# ZX_Distance_and_Gesture_Sensor.net
KiCad netlist of a schematic drawn in EAGLE
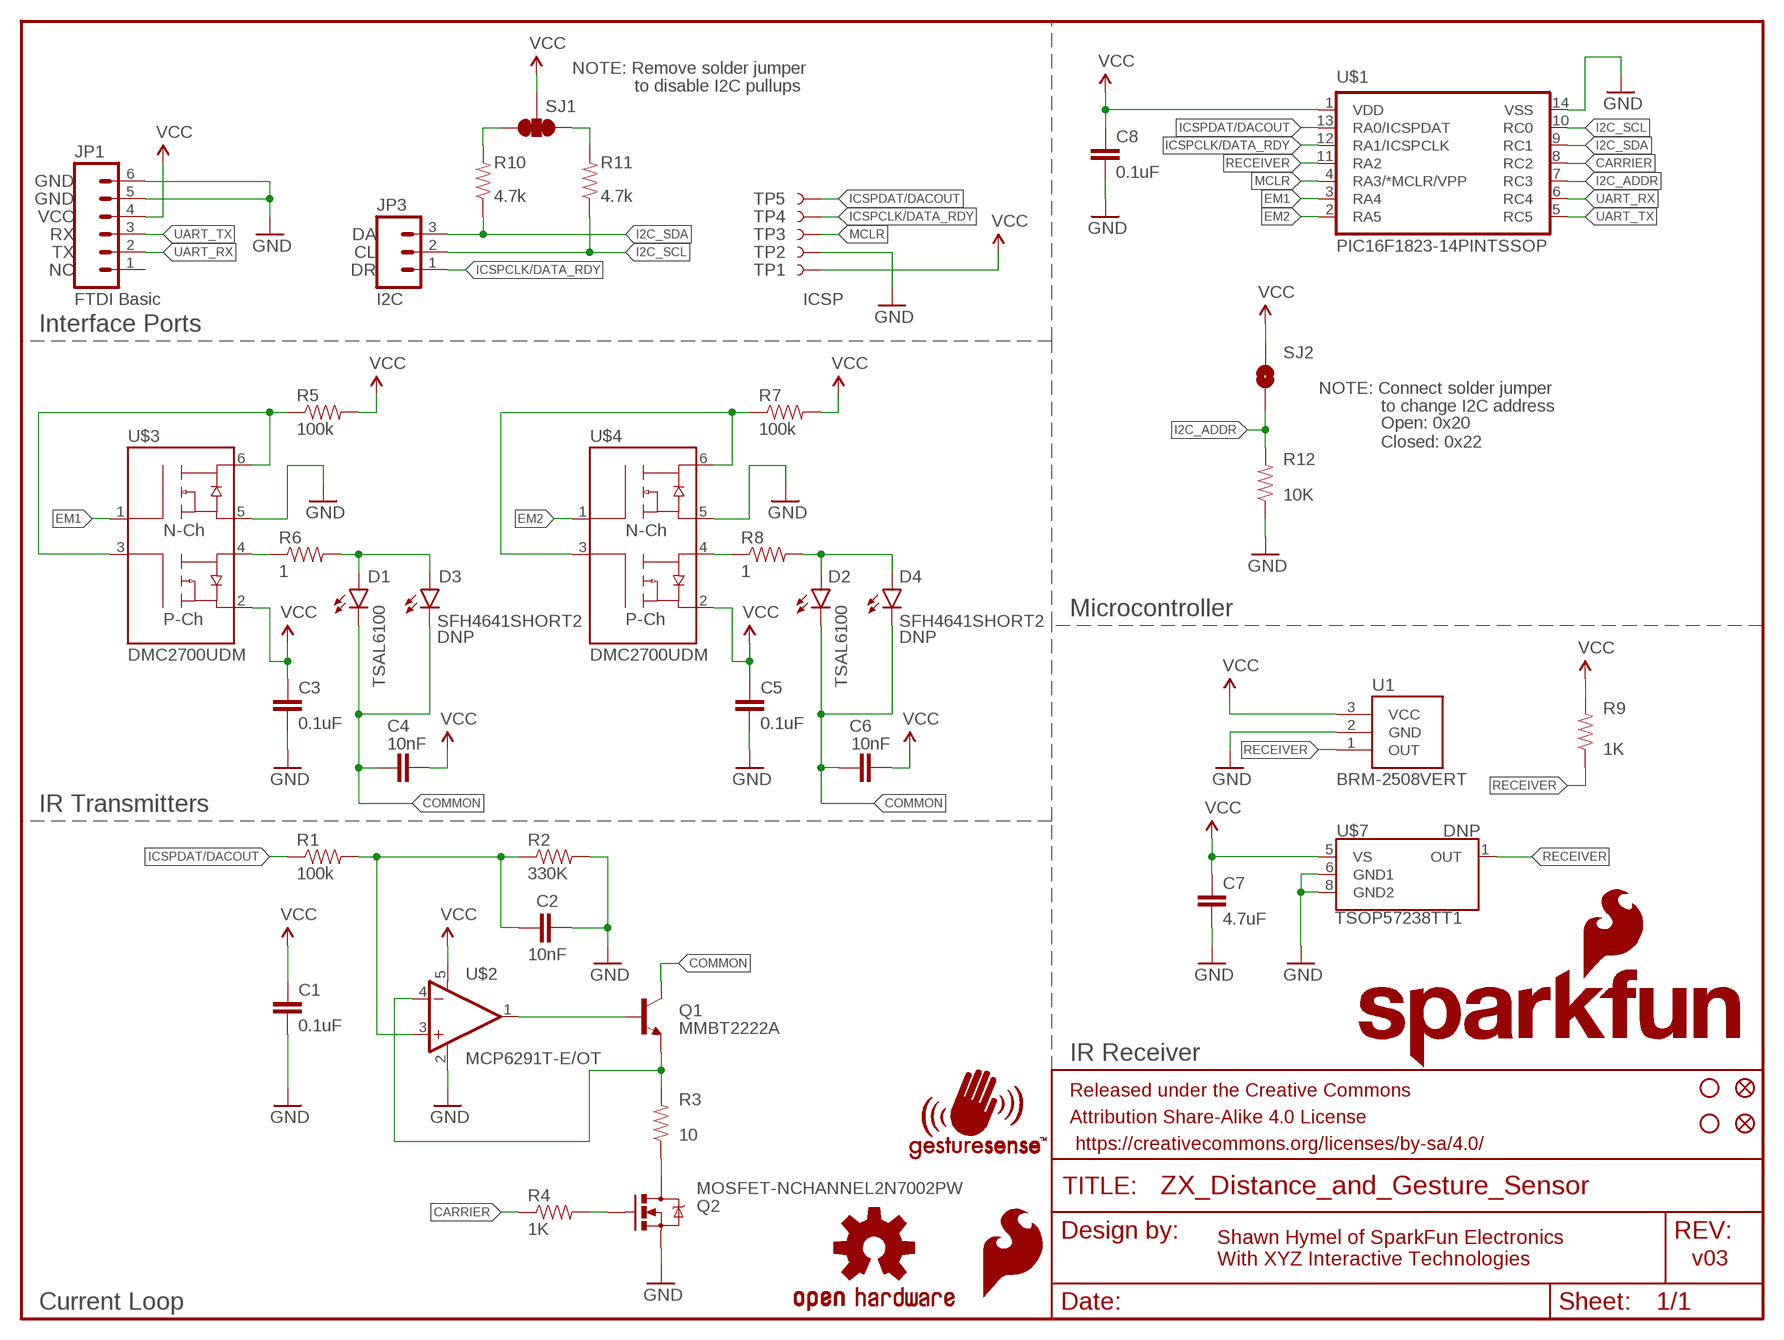
[diagram p0: schematic, sheet 1]

(export (version "E")
  (design (tool "Eeschema 10.0.6"))
  (components
    (comp (ref "C1")
      (value "0.1uF")
      (footprint "eagle-import:0603-CAP")
      (libsource (lib "eagle-import") (part "0.1UF-25V(+80/-20%)(0603)"))
    )
    (comp (ref "C2")
      (value "10nF")
      (footprint "eagle-import:0603-CAP")
      (libsource (lib "eagle-import") (part "10NF/10000PF-50V-10%(0603)"))
    )
    (comp (ref "C3")
      (value "0.1uF")
      (footprint "eagle-import:0603-CAP")
      (libsource (lib "eagle-import") (part "0.1UF-25V(+80/-20%)(0603)"))
    )
    (comp (ref "C4")
      (value "10nF")
      (footprint "eagle-import:0603-CAP")
      (libsource (lib "eagle-import") (part "10NF/10000PF-50V-10%(0603)"))
    )
    (comp (ref "C5")
      (value "0.1uF")
      (footprint "eagle-import:0603-CAP")
      (libsource (lib "eagle-import") (part "0.1UF-25V(+80/-20%)(0603)"))
    )
    (comp (ref "C6")
      (value "10nF")
      (footprint "eagle-import:0603-CAP")
      (libsource (lib "eagle-import") (part "10NF/10000PF-50V-10%(0603)"))
    )
    (comp (ref "C7")
      (value "4.7uF")
      (footprint "eagle-import:0603-CAP")
      (libsource (lib "eagle-import") (part "4.7UF-6.3V-10%(0603)0603"))
    )
    (comp (ref "C8")
      (value "0.1uF")
      (footprint "eagle-import:0603-CAP")
      (libsource (lib "eagle-import") (part "0.1UF-25V(+80/-20%)(0603)"))
    )
    (comp (ref "D1")
      (value "LED-IR-THRUTSAL6100")
      (footprint "eagle-import:LED5MM")
      (fields (field (name "VARIANT") "TSAL6100"))
      (libsource (lib "eagle-import") (part "LED-IR-THRUTSAL6100"))
    )
    (comp (ref "D2")
      (value "LED-IR-THRUTSAL6100")
      (footprint "eagle-import:LED5MM")
      (fields (field (name "VARIANT") "TSAL6100"))
      (libsource (lib "eagle-import") (part "LED-IR-THRUTSAL6100"))
    )
    (comp (ref "D3")
      (value "SFH4641SHORT2")
      (footprint "eagle-import:SFH4641-SHORT2")
      (libsource (lib "eagle-import") (part "SFH4641SHORT2"))
    )
    (comp (ref "D4")
      (value "SFH4641SHORT2")
      (footprint "eagle-import:SFH4641-SHORT2")
      (libsource (lib "eagle-import") (part "SFH4641SHORT2"))
    )
    (comp (ref "FID1")
      (value "FIDUCIAL1X2")
      (footprint "eagle-import:FIDUCIAL-1X2")
      (libsource (lib "eagle-import") (part "FIDUCIAL1X2"))
    )
    (comp (ref "FID2")
      (value "FIDUCIAL1X2")
      (footprint "eagle-import:FIDUCIAL-1X2")
      (libsource (lib "eagle-import") (part "FIDUCIAL1X2"))
    )
    (comp (ref "FRAME1")
      (value "FRAME-LETTER")
      (footprint "eagle-import:CREATIVE_COMMONS")
      (libsource (lib "eagle-import") (part "FRAME-LETTER"))
    )
    (comp (ref "JP1")
      (value "M06NO_SILK")
      (footprint "eagle-import:1X06_NO_SILK")
      (libsource (lib "eagle-import") (part "M06NO_SILK"))
    )
    (comp (ref "JP3")
      (value "M031X03_NO_SILK")
      (footprint "eagle-import:1X03_NO_SILK")
      (libsource (lib "eagle-import") (part "M031X03_NO_SILK"))
    )
    (comp (ref "LOGO1")
      (value "SFE_LOGO_FLAME.1_INCH")
      (footprint "eagle-import:SFE_LOGO_FLAME_.1")
      (libsource (lib "eagle-import") (part "SFE_LOGO_FLAME.1_INCH"))
    )
    (comp (ref "LOGO2")
      (value "OSHW-LOGOS")
      (footprint "eagle-import:OSHW-LOGO-S")
      (libsource (lib "eagle-import") (part "OSHW-LOGOS"))
    )
    (comp (ref "Q1")
      (value "MMBT2222A")
      (footprint "eagle-import:SOT23-3")
      (libsource (lib "eagle-import") (part "TRANSISTOR_NPNMMBT2222A"))
    )
    (comp (ref "Q2")
      (value "MOSFET-NCHANNEL2N7002PW")
      (footprint "eagle-import:SOT323")
      (libsource (lib "eagle-import") (part "MOSFET-NCHANNEL2N7002PW"))
    )
    (comp (ref "R1")
      (value "100k")
      (footprint "eagle-import:0603-RES")
      (libsource (lib "eagle-import") (part "100KOHM1/10W1%(0603)"))
    )
    (comp (ref "R2")
      (value "330K")
      (footprint "eagle-import:0603-RES")
      (libsource (lib "eagle-import") (part "330KOHM1/10W1%(0603)0603"))
    )
    (comp (ref "R3")
      (value "10")
      (footprint "eagle-import:0603-RES")
      (libsource (lib "eagle-import") (part "10OHM1/10W5%0603SMD"))
    )
    (comp (ref "R4")
      (value "1K")
      (footprint "eagle-import:0603-RES")
      (libsource (lib "eagle-import") (part "1KOHM1/10W1%(0603)"))
    )
    (comp (ref "R5")
      (value "100k")
      (footprint "eagle-import:0603-RES")
      (libsource (lib "eagle-import") (part "100KOHM1/10W1%(0603)"))
    )
    (comp (ref "R6")
      (value "1")
      (footprint "eagle-import:0603-RES")
      (libsource (lib "eagle-import") (part "1OHM1/10W1%(0603)"))
    )
    (comp (ref "R7")
      (value "100k")
      (footprint "eagle-import:0603-RES")
      (libsource (lib "eagle-import") (part "100KOHM1/10W1%(0603)"))
    )
    (comp (ref "R8")
      (value "1")
      (footprint "eagle-import:0603-RES")
      (libsource (lib "eagle-import") (part "1OHM1/10W1%(0603)"))
    )
    (comp (ref "R9")
      (value "1K")
      (footprint "eagle-import:0603-RES")
      (libsource (lib "eagle-import") (part "1KOHM1/10W1%(0603)"))
    )
    (comp (ref "R10")
      (value "4.7k")
      (footprint "eagle-import:0603")
      (libsource (lib "eagle-import") (part "4.7KOHM1/10W1%(0603)"))
    )
    (comp (ref "R11")
      (value "4.7k")
      (footprint "eagle-import:0603")
      (libsource (lib "eagle-import") (part "4.7KOHM1/10W1%(0603)"))
    )
    (comp (ref "R12")
      (value "10K")
      (footprint "eagle-import:0603-RES")
      (libsource (lib "eagle-import") (part "10KOHM1/10W1%(0603)0603"))
    )
    (comp (ref "SJ1")
      (value "SOLDERJUMPER_2WAYPASTE1&2&3")
      (footprint "eagle-import:SJ_3_PASTE1&2&3")
      (libsource (lib "eagle-import") (part "SOLDERJUMPER_2WAYPASTE1&2&3"))
    )
    (comp (ref "SJ2")
      (value "SOLDERJUMPERNO")
      (footprint "eagle-import:SJ_2S-NO")
      (libsource (lib "eagle-import") (part "SOLDERJUMPERNO"))
    )
    (comp (ref "STANDOFF1")
      (value "STAND-OFF")
      (footprint "eagle-import:STAND-OFF")
      (libsource (lib "eagle-import") (part "STAND-OFF"))
    )
    (comp (ref "STANDOFF2")
      (value "STAND-OFF")
      (footprint "eagle-import:STAND-OFF")
      (libsource (lib "eagle-import") (part "STAND-OFF"))
    )
    (comp (ref "TP1")
      (value "TEST-POINT3X4")
      (footprint "eagle-import:PAD.03X.04")
      (libsource (lib "eagle-import") (part "TEST-POINT3X4"))
    )
    (comp (ref "TP2")
      (value "TEST-POINT3X4")
      (footprint "eagle-import:PAD.03X.04")
      (libsource (lib "eagle-import") (part "TEST-POINT3X4"))
    )
    (comp (ref "TP3")
      (value "TEST-POINT3X4")
      (footprint "eagle-import:PAD.03X.04")
      (libsource (lib "eagle-import") (part "TEST-POINT3X4"))
    )
    (comp (ref "TP4")
      (value "TEST-POINT3X4")
      (footprint "eagle-import:PAD.03X.04")
      (libsource (lib "eagle-import") (part "TEST-POINT3X4"))
    )
    (comp (ref "TP5")
      (value "TEST-POINT3X4")
      (footprint "eagle-import:PAD.03X.04")
      (libsource (lib "eagle-import") (part "TEST-POINT3X4"))
    )
    (comp (ref "U$1")
      (value "PIC16F1823-14PINTSSOP")
      (footprint "eagle-import:TSSOP14")
      (libsource (lib "eagle-import") (part "PIC16F1823-14PINTSSOP"))
    )
    (comp (ref "U$2")
      (value "MCP6291T-E/OT")
      (footprint "eagle-import:SOT23-5")
      (libsource (lib "eagle-import") (part "MCP6291T-E/OT"))
    )
    (comp (ref "U$3")
      (value "DMC2700UDM")
      (footprint "eagle-import:SOT26")
      (libsource (lib "eagle-import") (part "DMC2700UDM"))
    )
    (comp (ref "U$4")
      (value "DMC2700UDM")
      (footprint "eagle-import:SOT26")
      (libsource (lib "eagle-import") (part "DMC2700UDM"))
    )
    (comp (ref "U$5")
      (value "SFE_LOGO_NAME_FLAME.1_INCH")
      (footprint "eagle-import:SFE_LOGO_NAME_FLAME_.1")
      (libsource (lib "eagle-import") (part "SFE_LOGO_NAME_FLAME.1_INCH"))
    )
    (comp (ref "U$6")
      (value "GESTURESENSE_LOGOSTEXT")
      (footprint "eagle-import:GESTURESENSE_TEXT")
      (libsource (lib "eagle-import") (part "GESTURESENSE_LOGOSTEXT"))
    )
    (comp (ref "U$7")
      (value "TSOP57238TT1")
      (footprint "eagle-import:TSOP572")
      (fields (field (name "PLACE") "DNP"))
      (libsource (lib "eagle-import") (part "TSOP57238TT1"))
    )
    (comp (ref "U1")
      (value "BRM-2508VERT")
      (footprint "eagle-import:BRM-2508_VERT")
      (libsource (lib "eagle-import") (part "BRM-2508VERT"))
    )
  )
  (nets
    (net (code "1") (name "CARRIER") (class "Default")
      (node (ref "R4") (pin "1") (pinfunction "1_1") (pintype "passive"))
      (node (ref "U$1") (pin "8") (pinfunction "RC2_8") (pintype "bidirectional"))
    )
    (net (code "2") (name "COMMON") (class "Default")
      (node (ref "C4") (pin "1") (pinfunction "1_1") (pintype "passive"))
      (node (ref "C6") (pin "1") (pinfunction "1_1") (pintype "passive"))
      (node (ref "D1") (pin "K") (pinfunction "C_K") (pintype "passive"))
      (node (ref "D2") (pin "K") (pinfunction "C_K") (pintype "passive"))
      (node (ref "D3") (pin "C") (pinfunction "C_C") (pintype "passive"))
      (node (ref "D4") (pin "C") (pinfunction "C_C") (pintype "passive"))
      (node (ref "Q1") (pin "3") (pinfunction "C_3") (pintype "passive"))
    )
    (net (code "3") (name "EM1") (class "Default")
      (node (ref "U$1") (pin "3") (pinfunction "RA4_3") (pintype "bidirectional"))
      (node (ref "U$3") (pin "1") (pinfunction "G1_1") (pintype "bidirectional"))
    )
    (net (code "4") (name "EM2") (class "Default")
      (node (ref "U$1") (pin "2") (pinfunction "RA5_2") (pintype "bidirectional"))
      (node (ref "U$4") (pin "1") (pinfunction "G1_1") (pintype "bidirectional"))
    )
    (net (code "5") (name "GND") (class "Default")
      (node (ref "C1") (pin "2") (pinfunction "2_2") (pintype "passive"))
      (node (ref "C2") (pin "2") (pinfunction "2_2") (pintype "passive"))
      (node (ref "C3") (pin "2") (pinfunction "2_2") (pintype "passive"))
      (node (ref "C5") (pin "2") (pinfunction "2_2") (pintype "passive"))
      (node (ref "C7") (pin "2") (pinfunction "2_2") (pintype "passive"))
      (node (ref "C8") (pin "2") (pinfunction "2_2") (pintype "passive"))
      (node (ref "JP1") (pin "5") (pinfunction "5_5") (pintype "passive"))
      (node (ref "JP1") (pin "6") (pinfunction "6_6") (pintype "passive"))
      (node (ref "Q2") (pin "2") (pinfunction "S_2") (pintype "passive"))
      (node (ref "R12") (pin "1") (pinfunction "1_1") (pintype "passive"))
      (node (ref "R2") (pin "2") (pinfunction "2_2") (pintype "passive"))
      (node (ref "TP2") (pin "P$1") (pinfunction "1_P$1") (pintype "bidirectional"))
      (node (ref "U$1") (pin "14") (pinfunction "VSS_14") (pintype "power_in"))
      (node (ref "U$2") (pin "2") (pinfunction "V-_2") (pintype "power_in"))
      (node (ref "U$3") (pin "5") (pinfunction "S1_5") (pintype "bidirectional"))
      (node (ref "U$4") (pin "5") (pinfunction "S1_5") (pintype "bidirectional"))
      (node (ref "U$7") (pin "6") (pinfunction "GND1_6") (pintype "bidirectional"))
      (node (ref "U$7") (pin "8") (pinfunction "GND2_8") (pintype "bidirectional"))
      (node (ref "U1") (pin "2") (pinfunction "GND_2") (pintype "bidirectional"))
    )
    (net (code "6") (name "I2C_ADDR") (class "Default")
      (node (ref "R12") (pin "2") (pinfunction "2_2") (pintype "passive"))
      (node (ref "SJ2") (pin "1") (pinfunction "1_1") (pintype "passive"))
      (node (ref "U$1") (pin "7") (pinfunction "RC3_7") (pintype "bidirectional"))
    )
    (net (code "7") (name "I2C_SCL") (class "Default")
      (node (ref "JP3") (pin "2") (pinfunction "2_2") (pintype "passive"))
      (node (ref "R11") (pin "1") (pinfunction "1_1") (pintype "passive"))
      (node (ref "U$1") (pin "10") (pinfunction "RC0_10") (pintype "bidirectional"))
    )
    (net (code "8") (name "I2C_SDA") (class "Default")
      (node (ref "JP3") (pin "3") (pinfunction "3_3") (pintype "passive"))
      (node (ref "R10") (pin "1") (pinfunction "1_1") (pintype "passive"))
      (node (ref "U$1") (pin "9") (pinfunction "RC1_9") (pintype "bidirectional"))
    )
    (net (code "9") (name "ICSPCLK{slash}DATA_RDY") (class "Default")
      (node (ref "JP3") (pin "1") (pinfunction "1_1") (pintype "passive"))
      (node (ref "TP4") (pin "P$1") (pinfunction "1_P$1") (pintype "bidirectional"))
      (node (ref "U$1") (pin "12") (pinfunction "RA1/ICSPCLK_12") (pintype "bidirectional"))
    )
    (net (code "10") (name "ICSPDAT{slash}DACOUT") (class "Default")
      (node (ref "R1") (pin "1") (pinfunction "1_1") (pintype "passive"))
      (node (ref "TP5") (pin "P$1") (pinfunction "1_P$1") (pintype "bidirectional"))
      (node (ref "U$1") (pin "13") (pinfunction "RA0/ICSPDAT_13") (pintype "bidirectional"))
    )
    (net (code "11") (name "MCLR") (class "Default")
      (node (ref "TP3") (pin "P$1") (pinfunction "1_P$1") (pintype "bidirectional"))
      (node (ref "U$1") (pin "4") (pinfunction "RA3/*MCLR/VPP_4") (pintype "input"))
    )
    (net (code "12") (name "Net-(D1-PadA)") (class "Default")
      (node (ref "D1") (pin "A") (pinfunction "A_A") (pintype "passive"))
      (node (ref "D3") (pin "A") (pinfunction "A_A") (pintype "passive"))
      (node (ref "R6") (pin "2") (pinfunction "2_2") (pintype "passive"))
    )
    (net (code "13") (name "Net-(D2-PadA)") (class "Default")
      (node (ref "D2") (pin "A") (pinfunction "A_A") (pintype "passive"))
      (node (ref "D4") (pin "A") (pinfunction "A_A") (pintype "passive"))
      (node (ref "R8") (pin "2") (pinfunction "2_2") (pintype "passive"))
    )
    (net (code "14") (name "Net-(Q1-B)") (class "Default")
      (node (ref "Q1") (pin "1") (pinfunction "B_1") (pintype "passive"))
      (node (ref "U$2") (pin "1") (pinfunction "OUT_1") (pintype "output"))
    )
    (net (code "15") (name "Net-(Q1-E)") (class "Default")
      (node (ref "Q1") (pin "2") (pinfunction "E_2") (pintype "passive"))
      (node (ref "R3") (pin "2") (pinfunction "2_2") (pintype "passive"))
      (node (ref "U$2") (pin "4") (pinfunction "-IN_4") (pintype "input"))
    )
    (net (code "16") (name "Net-(Q2-D)") (class "Default")
      (node (ref "Q2") (pin "3") (pinfunction "D_3") (pintype "passive"))
      (node (ref "R3") (pin "1") (pinfunction "1_1") (pintype "passive"))
    )
    (net (code "17") (name "Net-(Q2-G)") (class "Default")
      (node (ref "Q2") (pin "1") (pinfunction "G_1") (pintype "passive"))
      (node (ref "R4") (pin "2") (pinfunction "2_2") (pintype "passive"))
    )
    (net (code "18") (name "Net-(R10-Pad2)") (class "Default")
      (node (ref "R10") (pin "2") (pinfunction "2_2") (pintype "passive"))
      (node (ref "SJ1") (pin "3") (pinfunction "3_3") (pintype "passive"))
    )
    (net (code "19") (name "Net-(R11-Pad2)") (class "Default")
      (node (ref "R11") (pin "2") (pinfunction "2_2") (pintype "passive"))
      (node (ref "SJ1") (pin "1") (pinfunction "1_1") (pintype "passive"))
    )
    (net (code "20") (name "Net-(U$2-+IN)") (class "Default")
      (node (ref "C2") (pin "1") (pinfunction "1_1") (pintype "passive"))
      (node (ref "R1") (pin "2") (pinfunction "2_2") (pintype "passive"))
      (node (ref "R2") (pin "1") (pinfunction "1_1") (pintype "passive"))
      (node (ref "U$2") (pin "3") (pinfunction "+IN_3") (pintype "input"))
    )
    (net (code "21") (name "Net-(U$3-D1)") (class "Default")
      (node (ref "R5") (pin "1") (pinfunction "1_1") (pintype "passive"))
      (node (ref "U$3") (pin "3") (pinfunction "G2_3") (pintype "bidirectional"))
      (node (ref "U$3") (pin "6") (pinfunction "D1_6") (pintype "bidirectional"))
    )
    (net (code "22") (name "Net-(U$3-D2)") (class "Default")
      (node (ref "R6") (pin "1") (pinfunction "1_1") (pintype "passive"))
      (node (ref "U$3") (pin "4") (pinfunction "D2_4") (pintype "bidirectional"))
    )
    (net (code "23") (name "Net-(U$4-D1)") (class "Default")
      (node (ref "R7") (pin "1") (pinfunction "1_1") (pintype "passive"))
      (node (ref "U$4") (pin "3") (pinfunction "G2_3") (pintype "bidirectional"))
      (node (ref "U$4") (pin "6") (pinfunction "D1_6") (pintype "bidirectional"))
    )
    (net (code "24") (name "Net-(U$4-D2)") (class "Default")
      (node (ref "R8") (pin "1") (pinfunction "1_1") (pintype "passive"))
      (node (ref "U$4") (pin "4") (pinfunction "D2_4") (pintype "bidirectional"))
    )
    (net (code "25") (name "RECEIVER") (class "Default")
      (node (ref "R9") (pin "1") (pinfunction "1_1") (pintype "passive"))
      (node (ref "U$1") (pin "11") (pinfunction "RA2_11") (pintype "bidirectional"))
      (node (ref "U$7") (pin "1") (pinfunction "OUT_1") (pintype "bidirectional"))
      (node (ref "U1") (pin "1") (pinfunction "OUT_1") (pintype "bidirectional"))
    )
    (net (code "26") (name "UART_RX") (class "Default")
      (node (ref "JP1") (pin "2") (pinfunction "2_2") (pintype "passive"))
      (node (ref "U$1") (pin "6") (pinfunction "RC4_6") (pintype "bidirectional"))
    )
    (net (code "27") (name "UART_TX") (class "Default")
      (node (ref "JP1") (pin "3") (pinfunction "3_3") (pintype "passive"))
      (node (ref "U$1") (pin "5") (pinfunction "RC5_5") (pintype "bidirectional"))
    )
    (net (code "28") (name "VCC") (class "Default")
      (node (ref "C1") (pin "1") (pinfunction "1_1") (pintype "passive"))
      (node (ref "C3") (pin "1") (pinfunction "1_1") (pintype "passive"))
      (node (ref "C4") (pin "2") (pinfunction "2_2") (pintype "passive"))
      (node (ref "C5") (pin "1") (pinfunction "1_1") (pintype "passive"))
      (node (ref "C6") (pin "2") (pinfunction "2_2") (pintype "passive"))
      (node (ref "C7") (pin "1") (pinfunction "1_1") (pintype "passive"))
      (node (ref "C8") (pin "1") (pinfunction "1_1") (pintype "passive"))
      (node (ref "JP1") (pin "4") (pinfunction "4_4") (pintype "passive"))
      (node (ref "R5") (pin "2") (pinfunction "2_2") (pintype "passive"))
      (node (ref "R7") (pin "2") (pinfunction "2_2") (pintype "passive"))
      (node (ref "R9") (pin "2") (pinfunction "2_2") (pintype "passive"))
      (node (ref "SJ1") (pin "2") (pinfunction "2_2") (pintype "passive"))
      (node (ref "SJ2") (pin "2") (pinfunction "2_2") (pintype "passive"))
      (node (ref "TP1") (pin "P$1") (pinfunction "1_P$1") (pintype "bidirectional"))
      (node (ref "U$1") (pin "1") (pinfunction "VDD_1") (pintype "power_in"))
      (node (ref "U$2") (pin "5") (pinfunction "V+_5") (pintype "power_in"))
      (node (ref "U$3") (pin "2") (pinfunction "S2_2") (pintype "bidirectional"))
      (node (ref "U$4") (pin "2") (pinfunction "S2_2") (pintype "bidirectional"))
      (node (ref "U$7") (pin "5") (pinfunction "VS_5") (pintype "bidirectional"))
      (node (ref "U1") (pin "3") (pinfunction "VCC_3") (pintype "bidirectional"))
    )
    (net (code "29") (name "unconnected-(JP1-Pad1)") (class "Default")
      (node (ref "JP1") (pin "1") (pinfunction "1_1") (pintype "passive"))
    )
  )
)
